# schematic_draft_v1.net
KiCad netlist of a schematic drawn in EAGLE
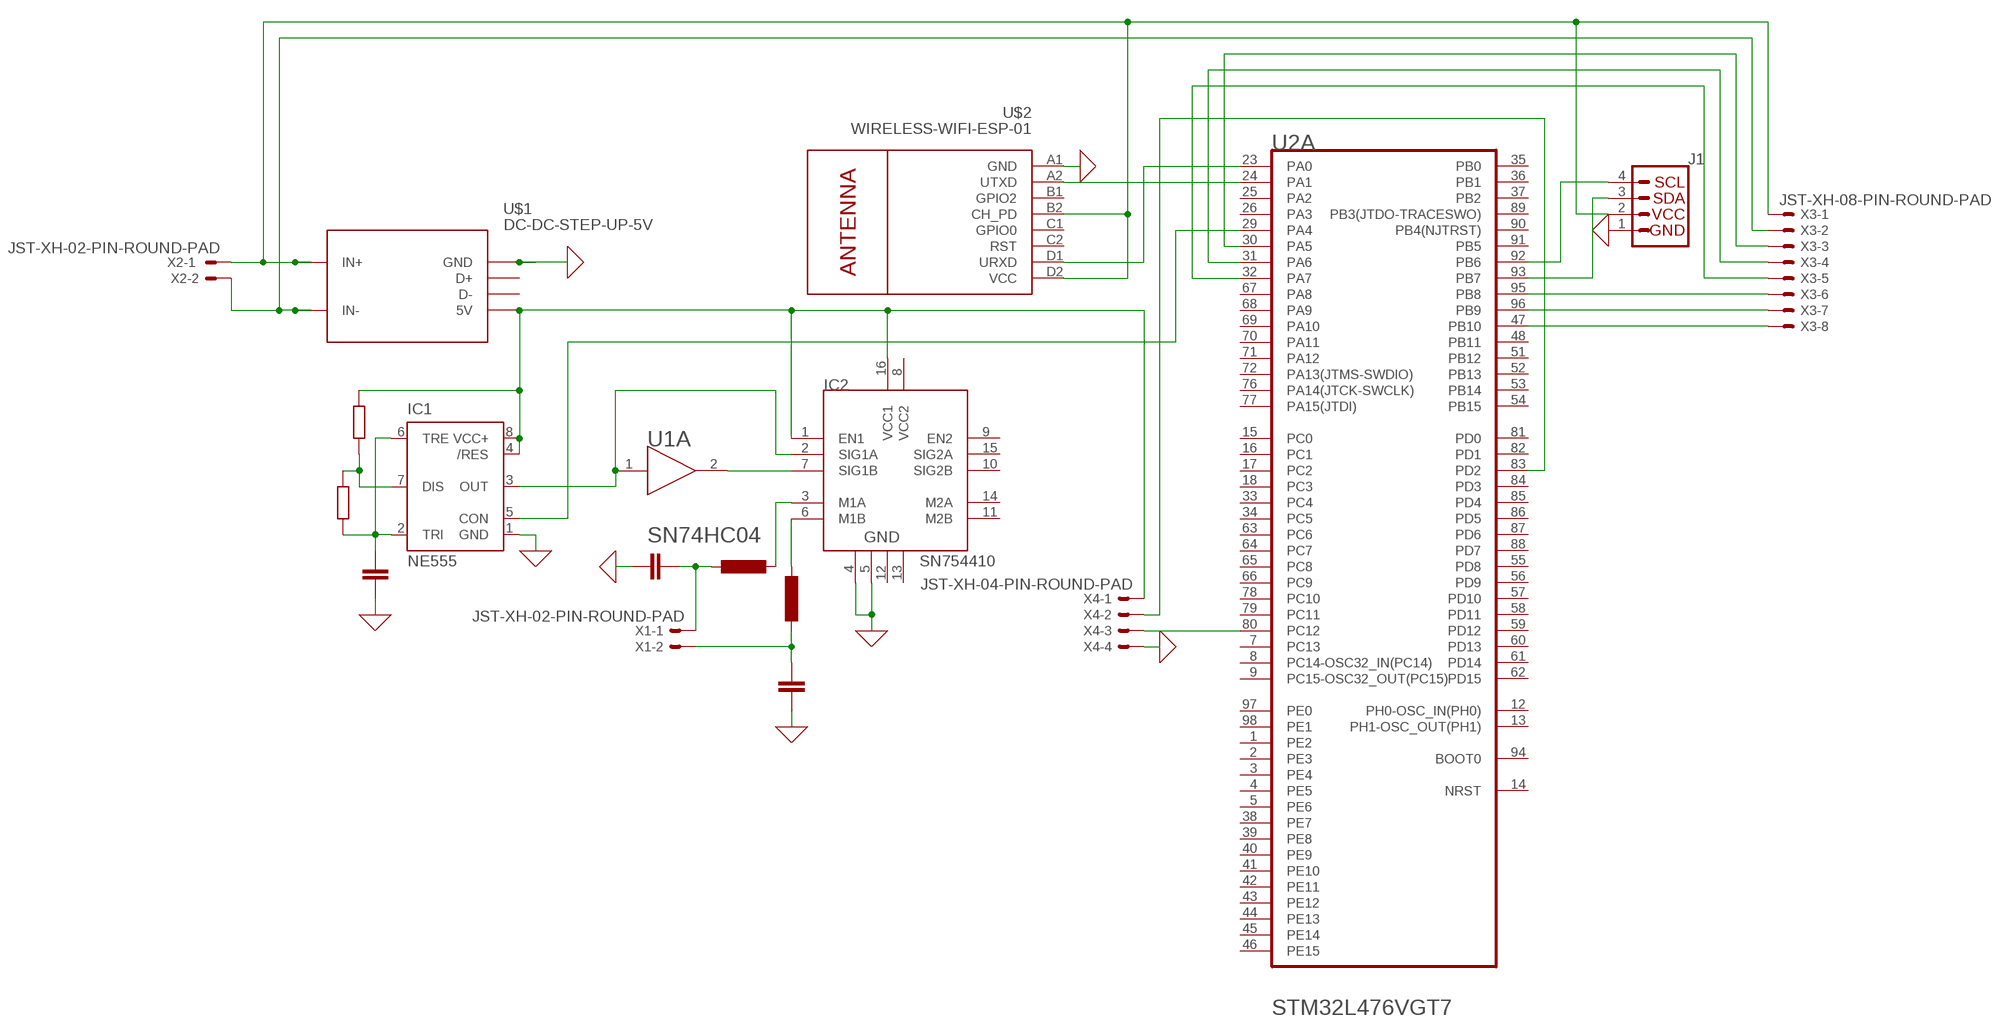
[diagram p0: schematic, sheet 1]

(export (version "E")
  (design (tool "Eeschema 10.0.6"))
  (components
    (comp (ref "IC1")
      (value "NE555")
      (footprint "eagle-import:DIL-08")
      (fields (field (name "MF") "Arrow Electronics") (field (name "MPN") "NE555N"))
      (libsource (lib "eagle-import") (part "NE555"))
    )
    (comp (ref "IC2")
      (value "SN754410")
      (footprint "eagle-import:DIP16")
      (libsource (lib "eagle-import") (part "SN754410"))
    )
    (comp (ref "J1")
      (value "QWIIC_CONNECTORJS-1MM")
      (footprint "eagle-import:1X04_1MM_RA")
      (libsource (lib "eagle-import") (part "QWIIC_CONNECTORJS-1MM"))
    )
    (comp (ref "U$1")
      (value "DC-DC-STEP-UP-5V")
      (footprint "eagle-import:DC-DC-STEP-UP-5V")
      (libsource (lib "eagle-import") (part "DC-DC-STEP-UP-5V"))
    )
    (comp (ref "U$2")
      (value "WIRELESS-WIFI-ESP-01")
      (footprint "eagle-import:WIRELESS-WIFI-ESP-01")
      (libsource (lib "eagle-import") (part "WIRELESS-WIFI-ESP-01"))
    )
    (comp (ref "U1")
      (value "TEXAS_INSTRUMENTS_SN74HC04TEXAS_INSTRUMENTS_SN74HC04_0_0")
      (footprint "eagle-import:TEXAS_INSTRUMENTS_SN74HC04_0")
      (fields (field (name "MF") "Texas Instruments") (field (name "MPN") "SN74HC04"))
      (libsource (lib "eagle-import") (part "TEXAS_INSTRUMENTS_SN74HC04TEXAS_INSTRUMENTS_SN74HC04_0_0"))
    )
    (comp (ref "U2")
      (value "STMICROELECTRONICS_STM32L476VGT7STMICROELECTRONICS_STM32L476VGT7_0_0")
      (footprint "eagle-import:STMICROELECTRONICS_STM32L476VGT7_0")
      (fields (field (name "MF") "STMicroelectronics") (field (name "MPN") "STM32L476VGT7"))
      (libsource (lib "eagle-import") (part "STMICROELECTRONICS_STM32L476VGT7STMICROELECTRONICS_STM32L476VGT7_0_0"))
    )
    (comp (ref "X1")
      (value "JST-XH-02-PIN-ROUND-PAD")
      (footprint "eagle-import:JST-XH-02-PACKAGE-ROUND-PAD")
      (libsource (lib "eagle-import") (part "JST-XH-02-PIN-ROUND-PAD"))
    )
    (comp (ref "X2")
      (value "JST-XH-02-PIN-ROUND-PAD")
      (footprint "eagle-import:JST-XH-02-PACKAGE-ROUND-PAD")
      (libsource (lib "eagle-import") (part "JST-XH-02-PIN-ROUND-PAD"))
    )
    (comp (ref "X3")
      (value "JST-XH-08-PIN-ROUND-PAD")
      (footprint "eagle-import:JST-XH-08-PACKAGE-ROUND-PAD")
      (libsource (lib "eagle-import") (part "JST-XH-08-PIN-ROUND-PAD"))
    )
    (comp (ref "X4")
      (value "JST-XH-04-PIN-ROUND-PAD")
      (footprint "eagle-import:JST-XH-04-PACKAGE-ROUND-PAD")
      (libsource (lib "eagle-import") (part "JST-XH-04-PIN-ROUND-PAD"))
    )
  )
  (nets
    (net (code "1") (name "/P12") (class "Default")
      (node (ref "IC2") (pin "12") (pinfunction "P12_12") (pintype "power_in"))
    )
    (net (code "2") (name "/P13") (class "Default")
      (node (ref "IC2") (pin "13") (pinfunction "P13_13") (pintype "power_in"))
    )
    (net (code "3") (name "/VCC2") (class "Default")
      (node (ref "IC2") (pin "8") (pinfunction "VCC2_8") (pintype "power_in"))
    )
    (net (code "4") (name "GND") (class "Default")
      (node (ref "IC1") (pin "1") (pinfunction "GND_1") (pintype "power_in"))
      (node (ref "IC2") (pin "4") (pinfunction "P4_4") (pintype "power_in"))
      (node (ref "IC2") (pin "5") (pinfunction "P5_5") (pintype "power_in"))
      (node (ref "J1") (pin "1") (pinfunction "GND_1") (pintype "power_in"))
      (node (ref "U$1") (pin "GND") (pinfunction "GND_GND") (pintype "bidirectional"))
      (node (ref "U$2") (pin "A1") (pinfunction "GND_A1") (pintype "power_in"))
      (node (ref "X4") (pin "4") (pinfunction "S_4") (pintype "passive"))
    )
    (net (code "5") (name "Net-(IC1-CON)") (class "Default")
      (node (ref "IC1") (pin "5") (pinfunction "CON_5") (pintype "input"))
      (node (ref "U2") (pin "29") (pinfunction "PA4_29") (pintype "bidirectional"))
    )
    (net (code "6") (name "Net-(IC1-OUT)") (class "Default")
      (node (ref "IC1") (pin "3") (pinfunction "OUT_3") (pintype "output"))
      (node (ref "IC2") (pin "2") (pinfunction "SIG1A_2") (pintype "bidirectional"))
      (node (ref "U1") (pin "1") (pinfunction "1A_1") (pintype "input"))
    )
    (net (code "7") (name "Net-(IC1-TRE)") (class "Default")
      (node (ref "IC1") (pin "2") (pinfunction "TRI_2") (pintype "input"))
      (node (ref "IC1") (pin "6") (pinfunction "TRE_6") (pintype "input"))
    )
    (net (code "8") (name "Net-(IC1-VCC+)") (class "Default")
      (node (ref "IC1") (pin "4") (pinfunction "/RES_4") (pintype "input"))
      (node (ref "IC1") (pin "8") (pinfunction "VCC+_8") (pintype "power_in"))
      (node (ref "IC2") (pin "1") (pinfunction "EN1_1") (pintype "bidirectional"))
      (node (ref "IC2") (pin "16") (pinfunction "VCC1_16") (pintype "power_in"))
      (node (ref "U$1") (pin "5V") (pinfunction "5V_5V") (pintype "bidirectional"))
      (node (ref "X4") (pin "1") (pinfunction "S_1") (pintype "passive"))
    )
    (net (code "9") (name "Net-(IC2-SIG1B)") (class "Default")
      (node (ref "IC2") (pin "7") (pinfunction "SIG1B_7") (pintype "bidirectional"))
      (node (ref "U1") (pin "2") (pinfunction "~{1Y}_2") (pintype "output"))
    )
    (net (code "10") (name "Net-(J1-SCL)") (class "Default")
      (node (ref "J1") (pin "4") (pinfunction "SCL_4") (pintype "passive"))
      (node (ref "U2") (pin "92") (pinfunction "PB6_92") (pintype "bidirectional"))
    )
    (net (code "11") (name "Net-(J1-SDA)") (class "Default")
      (node (ref "J1") (pin "3") (pinfunction "SDA_3") (pintype "passive"))
      (node (ref "U2") (pin "93") (pinfunction "PB7_93") (pintype "bidirectional"))
    )
    (net (code "12") (name "Net-(J1-VCC)") (class "Default")
      (node (ref "J1") (pin "2") (pinfunction "VCC_2") (pintype "power_in"))
      (node (ref "U$1") (pin "IN+") (pinfunction "IN+_IN+") (pintype "power_in"))
      (node (ref "U$2") (pin "B2") (pinfunction "CH_PD_B2") (pintype "bidirectional"))
      (node (ref "U$2") (pin "D2") (pinfunction "VCC_D2") (pintype "power_in"))
      (node (ref "X2") (pin "1") (pinfunction "S_1") (pintype "passive"))
      (node (ref "X3") (pin "1") (pinfunction "S_1") (pintype "passive"))
    )
    (net (code "13") (name "Net-(U$2-URXD)") (class "Default")
      (node (ref "U$2") (pin "D1") (pinfunction "URXD_D1") (pintype "bidirectional"))
      (node (ref "U2") (pin "23") (pinfunction "PA0_23") (pintype "bidirectional"))
    )
    (net (code "14") (name "Net-(U$2-UTXD)") (class "Default")
      (node (ref "U$2") (pin "A2") (pinfunction "UTXD_A2") (pintype "bidirectional"))
      (node (ref "U2") (pin "24") (pinfunction "PA1_24") (pintype "bidirectional"))
    )
    (net (code "15") (name "Net-(U2A-PA5)") (class "Default")
      (node (ref "U2") (pin "30") (pinfunction "PA5_30") (pintype "bidirectional"))
      (node (ref "X3") (pin "3") (pinfunction "S_3") (pintype "passive"))
    )
    (net (code "16") (name "Net-(U2A-PA6)") (class "Default")
      (node (ref "U2") (pin "31") (pinfunction "PA6_31") (pintype "bidirectional"))
      (node (ref "X3") (pin "4") (pinfunction "S_4") (pintype "passive"))
    )
    (net (code "17") (name "Net-(U2A-PA7)") (class "Default")
      (node (ref "U2") (pin "32") (pinfunction "PA7_32") (pintype "bidirectional"))
      (node (ref "X3") (pin "5") (pinfunction "S_5") (pintype "passive"))
    )
    (net (code "18") (name "Net-(U2A-PB8)") (class "Default")
      (node (ref "U2") (pin "95") (pinfunction "PB8_95") (pintype "bidirectional"))
      (node (ref "X3") (pin "6") (pinfunction "S_6") (pintype "passive"))
    )
    (net (code "19") (name "Net-(U2A-PB9)") (class "Default")
      (node (ref "U2") (pin "96") (pinfunction "PB9_96") (pintype "bidirectional"))
      (node (ref "X3") (pin "7") (pinfunction "S_7") (pintype "passive"))
    )
    (net (code "20") (name "Net-(U2A-PB10)") (class "Default")
      (node (ref "U2") (pin "47") (pinfunction "PB10_47") (pintype "bidirectional"))
      (node (ref "X3") (pin "8") (pinfunction "S_8") (pintype "passive"))
    )
    (net (code "21") (name "Net-(U2A-PC12)") (class "Default")
      (node (ref "U2") (pin "80") (pinfunction "PC12_80") (pintype "bidirectional"))
      (node (ref "X4") (pin "3") (pinfunction "S_3") (pintype "passive"))
    )
    (net (code "22") (name "Net-(U2A-PD2)") (class "Default")
      (node (ref "U2") (pin "83") (pinfunction "PD2_83") (pintype "bidirectional"))
      (node (ref "X4") (pin "2") (pinfunction "S_2") (pintype "passive"))
    )
    (net (code "23") (name "Net-(X2B-S)") (class "Default")
      (node (ref "U$1") (pin "IN-") (pinfunction "IN-_IN-") (pintype "power_in"))
      (node (ref "X2") (pin "2") (pinfunction "S_2") (pintype "passive"))
      (node (ref "X3") (pin "2") (pinfunction "S_2") (pintype "passive"))
    )
    (net (code "24") (name "unconnected-(IC1-DIS-Pad7)") (class "Default")
      (node (ref "IC1") (pin "7") (pinfunction "DIS_7") (pintype "input"))
    )
    (net (code "25") (name "unconnected-(IC2-EN2-Pad9)") (class "Default")
      (node (ref "IC2") (pin "9") (pinfunction "EN2_9") (pintype "bidirectional"))
    )
    (net (code "26") (name "unconnected-(IC2-M1A-Pad3)") (class "Default")
      (node (ref "IC2") (pin "3") (pinfunction "M1A_3") (pintype "bidirectional"))
    )
    (net (code "27") (name "unconnected-(IC2-M1B-Pad6)") (class "Default")
      (node (ref "IC2") (pin "6") (pinfunction "M1B_6") (pintype "bidirectional"))
    )
    (net (code "28") (name "unconnected-(IC2-M2A-Pad14)") (class "Default")
      (node (ref "IC2") (pin "14") (pinfunction "M2A_14") (pintype "bidirectional"))
    )
    (net (code "29") (name "unconnected-(IC2-M2B-Pad11)") (class "Default")
      (node (ref "IC2") (pin "11") (pinfunction "M2B_11") (pintype "bidirectional"))
    )
    (net (code "30") (name "unconnected-(IC2-SIG2A-Pad15)") (class "Default")
      (node (ref "IC2") (pin "15") (pinfunction "SIG2A_15") (pintype "bidirectional"))
    )
    (net (code "31") (name "unconnected-(IC2-SIG2B-Pad10)") (class "Default")
      (node (ref "IC2") (pin "10") (pinfunction "SIG2B_10") (pintype "bidirectional"))
    )
    (net (code "32") (name "unconnected-(U$1-PadD+)") (class "Default")
      (node (ref "U$1") (pin "D+") (pinfunction "D+_D+") (pintype "bidirectional"))
    )
    (net (code "33") (name "unconnected-(U$1-PadD-)") (class "Default")
      (node (ref "U$1") (pin "D-") (pinfunction "D-_D-") (pintype "bidirectional"))
    )
    (net (code "34") (name "unconnected-(U$2-GPIO0-PadC1)") (class "Default")
      (node (ref "U$2") (pin "C1") (pinfunction "GPIO0_C1") (pintype "bidirectional"))
    )
    (net (code "35") (name "unconnected-(U$2-GPIO2-PadB1)") (class "Default")
      (node (ref "U$2") (pin "B1") (pinfunction "GPIO2_B1") (pintype "bidirectional"))
    )
    (net (code "36") (name "unconnected-(U$2-RST-PadC2)") (class "Default")
      (node (ref "U$2") (pin "C2") (pinfunction "RST_C2") (pintype "bidirectional"))
    )
    (net (code "37") (name "unconnected-(U2A-BOOT0-Pad94)") (class "Default")
      (node (ref "U2") (pin "94") (pinfunction "BOOT0_94") (pintype "input"))
    )
    (net (code "38") (name "unconnected-(U2A-NRST-Pad14)") (class "Default")
      (node (ref "U2") (pin "14") (pinfunction "NRST_14") (pintype "bidirectional"))
    )
    (net (code "39") (name "unconnected-(U2A-PA2-Pad25)") (class "Default")
      (node (ref "U2") (pin "25") (pinfunction "PA2_25") (pintype "bidirectional"))
    )
    (net (code "40") (name "unconnected-(U2A-PA3-Pad26)") (class "Default")
      (node (ref "U2") (pin "26") (pinfunction "PA3_26") (pintype "bidirectional"))
    )
    (net (code "41") (name "unconnected-(U2A-PA8-Pad67)") (class "Default")
      (node (ref "U2") (pin "67") (pinfunction "PA8_67") (pintype "bidirectional"))
    )
    (net (code "42") (name "unconnected-(U2A-PA9-Pad68)") (class "Default")
      (node (ref "U2") (pin "68") (pinfunction "PA9_68") (pintype "bidirectional"))
    )
    (net (code "43") (name "unconnected-(U2A-PA10-Pad69)") (class "Default")
      (node (ref "U2") (pin "69") (pinfunction "PA10_69") (pintype "bidirectional"))
    )
    (net (code "44") (name "unconnected-(U2A-PA11-Pad70)") (class "Default")
      (node (ref "U2") (pin "70") (pinfunction "PA11_70") (pintype "bidirectional"))
    )
    (net (code "45") (name "unconnected-(U2A-PA12-Pad71)") (class "Default")
      (node (ref "U2") (pin "71") (pinfunction "PA12_71") (pintype "bidirectional"))
    )
    (net (code "46") (name "unconnected-(U2A-PA13(JTMS-SWDIO)-Pad72)") (class "Default")
      (node (ref "U2") (pin "72") (pinfunction "PA13(JTMS-SWDIO)_72") (pintype "bidirectional"))
    )
    (net (code "47") (name "unconnected-(U2A-PA14(JTCK-SWCLK)-Pad76)") (class "Default")
      (node (ref "U2") (pin "76") (pinfunction "PA14(JTCK-SWCLK)_76") (pintype "bidirectional"))
    )
    (net (code "48") (name "unconnected-(U2A-PA15(JTDI)-Pad77)") (class "Default")
      (node (ref "U2") (pin "77") (pinfunction "PA15(JTDI)_77") (pintype "bidirectional"))
    )
    (net (code "49") (name "unconnected-(U2A-PB0-Pad35)") (class "Default")
      (node (ref "U2") (pin "35") (pinfunction "PB0_35") (pintype "bidirectional"))
    )
    (net (code "50") (name "unconnected-(U2A-PB1-Pad36)") (class "Default")
      (node (ref "U2") (pin "36") (pinfunction "PB1_36") (pintype "bidirectional"))
    )
    (net (code "51") (name "unconnected-(U2A-PB2-Pad37)") (class "Default")
      (node (ref "U2") (pin "37") (pinfunction "PB2_37") (pintype "bidirectional"))
    )
    (net (code "52") (name "unconnected-(U2A-PB3(JTDO-TRACESWO)-Pad89)") (class "Default")
      (node (ref "U2") (pin "89") (pinfunction "PB3(JTDO-TRACESWO)_89") (pintype "bidirectional"))
    )
    (net (code "53") (name "unconnected-(U2A-PB4(NJTRST)-Pad90)") (class "Default")
      (node (ref "U2") (pin "90") (pinfunction "PB4(NJTRST)_90") (pintype "bidirectional"))
    )
    (net (code "54") (name "unconnected-(U2A-PB5-Pad91)") (class "Default")
      (node (ref "U2") (pin "91") (pinfunction "PB5_91") (pintype "bidirectional"))
    )
    (net (code "55") (name "unconnected-(U2A-PB11-Pad48)") (class "Default")
      (node (ref "U2") (pin "48") (pinfunction "PB11_48") (pintype "bidirectional"))
    )
    (net (code "56") (name "unconnected-(U2A-PB12-Pad51)") (class "Default")
      (node (ref "U2") (pin "51") (pinfunction "PB12_51") (pintype "bidirectional"))
    )
    (net (code "57") (name "unconnected-(U2A-PB13-Pad52)") (class "Default")
      (node (ref "U2") (pin "52") (pinfunction "PB13_52") (pintype "bidirectional"))
    )
    (net (code "58") (name "unconnected-(U2A-PB14-Pad53)") (class "Default")
      (node (ref "U2") (pin "53") (pinfunction "PB14_53") (pintype "bidirectional"))
    )
    (net (code "59") (name "unconnected-(U2A-PB15-Pad54)") (class "Default")
      (node (ref "U2") (pin "54") (pinfunction "PB15_54") (pintype "bidirectional"))
    )
    (net (code "60") (name "unconnected-(U2A-PC0-Pad15)") (class "Default")
      (node (ref "U2") (pin "15") (pinfunction "PC0_15") (pintype "bidirectional"))
    )
    (net (code "61") (name "unconnected-(U2A-PC1-Pad16)") (class "Default")
      (node (ref "U2") (pin "16") (pinfunction "PC1_16") (pintype "bidirectional"))
    )
    (net (code "62") (name "unconnected-(U2A-PC2-Pad17)") (class "Default")
      (node (ref "U2") (pin "17") (pinfunction "PC2_17") (pintype "bidirectional"))
    )
    (net (code "63") (name "unconnected-(U2A-PC3-Pad18)") (class "Default")
      (node (ref "U2") (pin "18") (pinfunction "PC3_18") (pintype "bidirectional"))
    )
    (net (code "64") (name "unconnected-(U2A-PC4-Pad33)") (class "Default")
      (node (ref "U2") (pin "33") (pinfunction "PC4_33") (pintype "bidirectional"))
    )
    (net (code "65") (name "unconnected-(U2A-PC5-Pad34)") (class "Default")
      (node (ref "U2") (pin "34") (pinfunction "PC5_34") (pintype "bidirectional"))
    )
    (net (code "66") (name "unconnected-(U2A-PC6-Pad63)") (class "Default")
      (node (ref "U2") (pin "63") (pinfunction "PC6_63") (pintype "bidirectional"))
    )
    (net (code "67") (name "unconnected-(U2A-PC7-Pad64)") (class "Default")
      (node (ref "U2") (pin "64") (pinfunction "PC7_64") (pintype "bidirectional"))
    )
    (net (code "68") (name "unconnected-(U2A-PC8-Pad65)") (class "Default")
      (node (ref "U2") (pin "65") (pinfunction "PC8_65") (pintype "bidirectional"))
    )
    (net (code "69") (name "unconnected-(U2A-PC9-Pad66)") (class "Default")
      (node (ref "U2") (pin "66") (pinfunction "PC9_66") (pintype "bidirectional"))
    )
    (net (code "70") (name "unconnected-(U2A-PC10-Pad78)") (class "Default")
      (node (ref "U2") (pin "78") (pinfunction "PC10_78") (pintype "bidirectional"))
    )
    (net (code "71") (name "unconnected-(U2A-PC11-Pad79)") (class "Default")
      (node (ref "U2") (pin "79") (pinfunction "PC11_79") (pintype "bidirectional"))
    )
    (net (code "72") (name "unconnected-(U2A-PC13-Pad7)") (class "Default")
      (node (ref "U2") (pin "7") (pinfunction "PC13_7") (pintype "bidirectional"))
    )
    (net (code "73") (name "unconnected-(U2A-PC14-OSC32_IN(PC14)-Pad8)") (class "Default")
      (node (ref "U2") (pin "8") (pinfunction "PC14-OSC32_IN(PC14)_8") (pintype "bidirectional"))
    )
    (net (code "74") (name "unconnected-(U2A-PC15-OSC32_OUT(PC15)-Pad9)") (class "Default")
      (node (ref "U2") (pin "9") (pinfunction "PC15-OSC32_OUT(PC15)_9") (pintype "bidirectional"))
    )
    (net (code "75") (name "unconnected-(U2A-PD0-Pad81)") (class "Default")
      (node (ref "U2") (pin "81") (pinfunction "PD0_81") (pintype "bidirectional"))
    )
    (net (code "76") (name "unconnected-(U2A-PD1-Pad82)") (class "Default")
      (node (ref "U2") (pin "82") (pinfunction "PD1_82") (pintype "bidirectional"))
    )
    (net (code "77") (name "unconnected-(U2A-PD3-Pad84)") (class "Default")
      (node (ref "U2") (pin "84") (pinfunction "PD3_84") (pintype "bidirectional"))
    )
    (net (code "78") (name "unconnected-(U2A-PD4-Pad85)") (class "Default")
      (node (ref "U2") (pin "85") (pinfunction "PD4_85") (pintype "bidirectional"))
    )
    (net (code "79") (name "unconnected-(U2A-PD5-Pad86)") (class "Default")
      (node (ref "U2") (pin "86") (pinfunction "PD5_86") (pintype "bidirectional"))
    )
    (net (code "80") (name "unconnected-(U2A-PD6-Pad87)") (class "Default")
      (node (ref "U2") (pin "87") (pinfunction "PD6_87") (pintype "bidirectional"))
    )
    (net (code "81") (name "unconnected-(U2A-PD7-Pad88)") (class "Default")
      (node (ref "U2") (pin "88") (pinfunction "PD7_88") (pintype "bidirectional"))
    )
    (net (code "82") (name "unconnected-(U2A-PD8-Pad55)") (class "Default")
      (node (ref "U2") (pin "55") (pinfunction "PD8_55") (pintype "bidirectional"))
    )
    (net (code "83") (name "unconnected-(U2A-PD9-Pad56)") (class "Default")
      (node (ref "U2") (pin "56") (pinfunction "PD9_56") (pintype "bidirectional"))
    )
    (net (code "84") (name "unconnected-(U2A-PD10-Pad57)") (class "Default")
      (node (ref "U2") (pin "57") (pinfunction "PD10_57") (pintype "bidirectional"))
    )
    (net (code "85") (name "unconnected-(U2A-PD11-Pad58)") (class "Default")
      (node (ref "U2") (pin "58") (pinfunction "PD11_58") (pintype "bidirectional"))
    )
    (net (code "86") (name "unconnected-(U2A-PD12-Pad59)") (class "Default")
      (node (ref "U2") (pin "59") (pinfunction "PD12_59") (pintype "bidirectional"))
    )
    (net (code "87") (name "unconnected-(U2A-PD13-Pad60)") (class "Default")
      (node (ref "U2") (pin "60") (pinfunction "PD13_60") (pintype "bidirectional"))
    )
    (net (code "88") (name "unconnected-(U2A-PD14-Pad61)") (class "Default")
      (node (ref "U2") (pin "61") (pinfunction "PD14_61") (pintype "bidirectional"))
    )
    (net (code "89") (name "unconnected-(U2A-PD15-Pad62)") (class "Default")
      (node (ref "U2") (pin "62") (pinfunction "PD15_62") (pintype "bidirectional"))
    )
    (net (code "90") (name "unconnected-(U2A-PE0-Pad97)") (class "Default")
      (node (ref "U2") (pin "97") (pinfunction "PE0_97") (pintype "bidirectional"))
    )
    (net (code "91") (name "unconnected-(U2A-PE1-Pad98)") (class "Default")
      (node (ref "U2") (pin "98") (pinfunction "PE1_98") (pintype "bidirectional"))
    )
    (net (code "92") (name "unconnected-(U2A-PE2-Pad1)") (class "Default")
      (node (ref "U2") (pin "1") (pinfunction "PE2_1") (pintype "bidirectional"))
    )
    (net (code "93") (name "unconnected-(U2A-PE3-Pad2)") (class "Default")
      (node (ref "U2") (pin "2") (pinfunction "PE3_2") (pintype "bidirectional"))
    )
    (net (code "94") (name "unconnected-(U2A-PE4-Pad3)") (class "Default")
      (node (ref "U2") (pin "3") (pinfunction "PE4_3") (pintype "bidirectional"))
    )
    (net (code "95") (name "unconnected-(U2A-PE5-Pad4)") (class "Default")
      (node (ref "U2") (pin "4") (pinfunction "PE5_4") (pintype "bidirectional"))
    )
    (net (code "96") (name "unconnected-(U2A-PE6-Pad5)") (class "Default")
      (node (ref "U2") (pin "5") (pinfunction "PE6_5") (pintype "bidirectional"))
    )
    (net (code "97") (name "unconnected-(U2A-PE7-Pad38)") (class "Default")
      (node (ref "U2") (pin "38") (pinfunction "PE7_38") (pintype "bidirectional"))
    )
    (net (code "98") (name "unconnected-(U2A-PE8-Pad39)") (class "Default")
      (node (ref "U2") (pin "39") (pinfunction "PE8_39") (pintype "bidirectional"))
    )
    (net (code "99") (name "unconnected-(U2A-PE9-Pad40)") (class "Default")
      (node (ref "U2") (pin "40") (pinfunction "PE9_40") (pintype "bidirectional"))
    )
    (net (code "100") (name "unconnected-(U2A-PE10-Pad41)") (class "Default")
      (node (ref "U2") (pin "41") (pinfunction "PE10_41") (pintype "bidirectional"))
    )
    (net (code "101") (name "unconnected-(U2A-PE11-Pad42)") (class "Default")
      (node (ref "U2") (pin "42") (pinfunction "PE11_42") (pintype "bidirectional"))
    )
    (net (code "102") (name "unconnected-(U2A-PE12-Pad43)") (class "Default")
      (node (ref "U2") (pin "43") (pinfunction "PE12_43") (pintype "bidirectional"))
    )
    (net (code "103") (name "unconnected-(U2A-PE13-Pad44)") (class "Default")
      (node (ref "U2") (pin "44") (pinfunction "PE13_44") (pintype "bidirectional"))
    )
    (net (code "104") (name "unconnected-(U2A-PE14-Pad45)") (class "Default")
      (node (ref "U2") (pin "45") (pinfunction "PE14_45") (pintype "bidirectional"))
    )
    (net (code "105") (name "unconnected-(U2A-PE15-Pad46)") (class "Default")
      (node (ref "U2") (pin "46") (pinfunction "PE15_46") (pintype "bidirectional"))
    )
    (net (code "106") (name "unconnected-(U2A-PH0-OSC_IN(PH0)-Pad12)") (class "Default")
      (node (ref "U2") (pin "12") (pinfunction "PH0-OSC_IN(PH0)_12") (pintype "bidirectional"))
    )
    (net (code "107") (name "unconnected-(U2A-PH1-OSC_OUT(PH1)-Pad13)") (class "Default")
      (node (ref "U2") (pin "13") (pinfunction "PH1-OSC_OUT(PH1)_13") (pintype "bidirectional"))
    )
    (net (code "108") (name "unconnected-(X1A-S-Pad1)") (class "Default")
      (node (ref "X1") (pin "1") (pinfunction "S_1") (pintype "passive"))
    )
    (net (code "109") (name "unconnected-(X1B-S-Pad2)") (class "Default")
      (node (ref "X1") (pin "2") (pinfunction "S_2") (pintype "passive"))
    )
  )
)
